# rs422.net
KiCad netlist of a schematic drawn in EAGLE
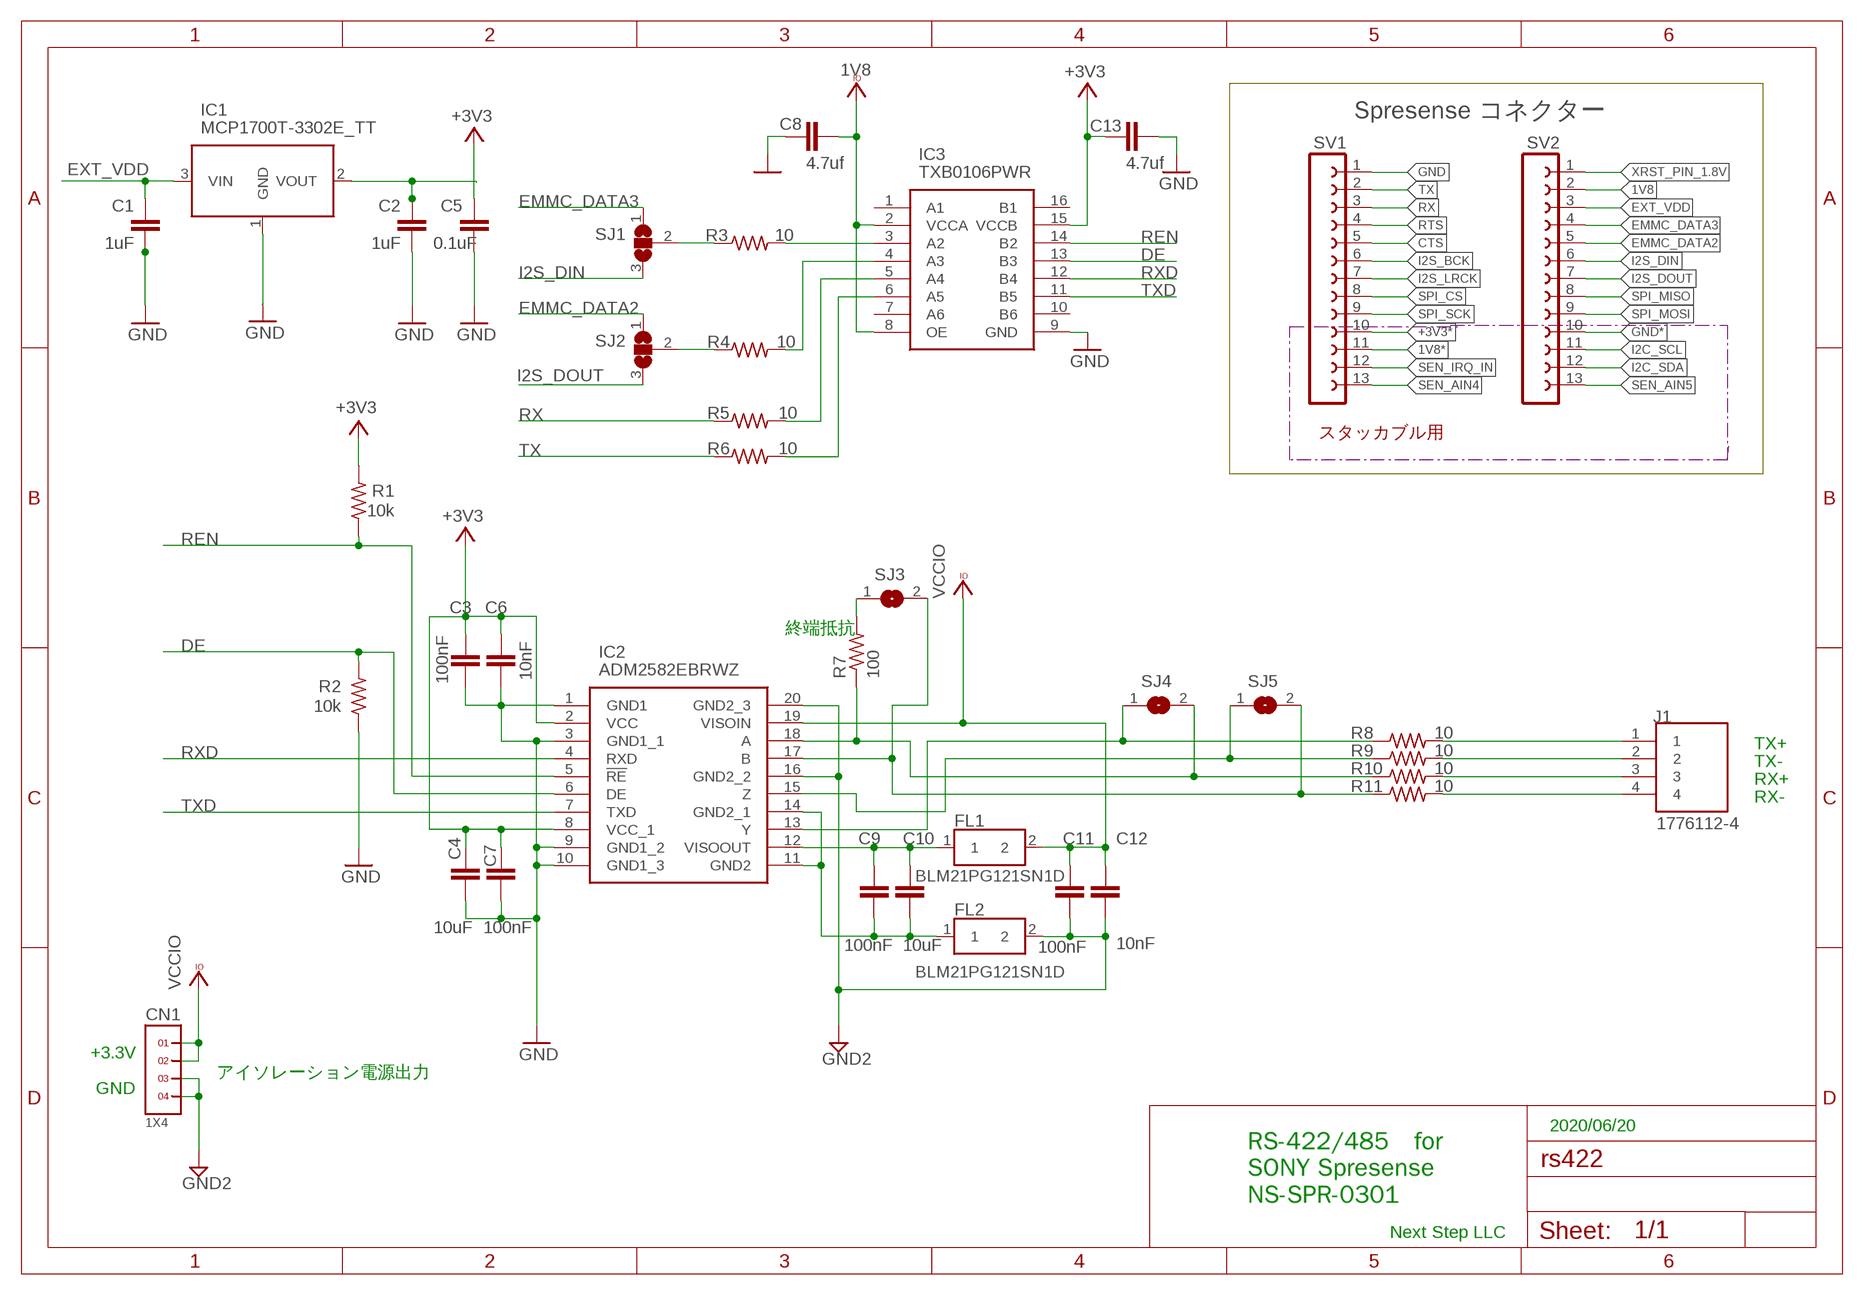
[diagram p0: schematic, sheet 1]

(export (version "E")
  (design (tool "Eeschema 10.0.6"))
  (components
    (comp (ref "C1")
      (value "1uF")
      (footprint "eagle-import:C0603K")
      (libsource (lib "eagle-import") (part "C-EUC0603K"))
    )
    (comp (ref "C2")
      (value "1uF")
      (footprint "eagle-import:C0603K")
      (libsource (lib "eagle-import") (part "C-EUC0603K"))
    )
    (comp (ref "C3")
      (value "100nF")
      (footprint "eagle-import:C0603K")
      (libsource (lib "eagle-import") (part "C-EUC0603K"))
    )
    (comp (ref "C4")
      (value "10uF")
      (footprint "eagle-import:C0603K")
      (libsource (lib "eagle-import") (part "C-EUC0603K"))
    )
    (comp (ref "C5")
      (value "0.1uF")
      (footprint "eagle-import:C0603K")
      (libsource (lib "eagle-import") (part "C-EUC0603K"))
    )
    (comp (ref "C6")
      (value "10nF")
      (footprint "eagle-import:C0603K")
      (libsource (lib "eagle-import") (part "C-EUC0603K"))
    )
    (comp (ref "C7")
      (value "100nF")
      (footprint "eagle-import:C0603K")
      (libsource (lib "eagle-import") (part "C-EUC0603K"))
    )
    (comp (ref "C8")
      (value "4.7uf")
      (footprint "eagle-import:C0603K")
      (libsource (lib "eagle-import") (part "C-EUC0603K"))
    )
    (comp (ref "C9")
      (value "100nF")
      (footprint "eagle-import:C0603K")
      (libsource (lib "eagle-import") (part "C-EUC0603K"))
    )
    (comp (ref "C10")
      (value "10uF")
      (footprint "eagle-import:C0603K")
      (libsource (lib "eagle-import") (part "C-EUC0603K"))
    )
    (comp (ref "C11")
      (value "100nF")
      (footprint "eagle-import:C0603K")
      (libsource (lib "eagle-import") (part "C-EUC0603K"))
    )
    (comp (ref "C12")
      (value "10nF")
      (footprint "eagle-import:C0603K")
      (libsource (lib "eagle-import") (part "C-EUC0603K"))
    )
    (comp (ref "C13")
      (value "4.7uf")
      (footprint "eagle-import:C0603K")
      (libsource (lib "eagle-import") (part "C-EUC0603K"))
    )
    (comp (ref "CN1")
      (value "1X4")
      (footprint "eagle-import:1X4")
      (libsource (lib "eagle-import") (part "1X4"))
    )
    (comp (ref "FL1")
      (value "BLM21PG121SN1D")
      (footprint "eagle-import:BEADC2012X105N")
      (fields (field (name "MOUSER_PART_NUMBER") "81-BLM21PG121SN1D"))
      (libsource (lib "eagle-import") (part "BLM21PG121SN1D"))
    )
    (comp (ref "FL2")
      (value "BLM21PG121SN1D")
      (footprint "eagle-import:BEADC2012X105N")
      (fields (field (name "MOUSER_PART_NUMBER") "81-BLM21PG121SN1D"))
      (libsource (lib "eagle-import") (part "BLM21PG121SN1D"))
    )
    (comp (ref "IC1")
      (value "MCP1700T-3302E_TT")
      (footprint "eagle-import:SOT95P237X112-3N")
      (fields
        (field (name "MANUFACTURER_PART_NUMBER") "MCP1700T-3302E/TT")
        (field (name "MOUSER_PART_NUMBER") "579-MCP1700T3302E/TT")
      )
      (libsource (lib "eagle-import") (part "MCP1700T-3302E_TT"))
    )
    (comp (ref "IC2")
      (value "ADM2582EBRWZ")
      (footprint "eagle-import:SOIC127P1032X265-20N")
      (fields (field (name "MOUSER_PART_NUMBER") "584-ADM2582EBRWZ"))
      (libsource (lib "eagle-import") (part "ADM2582EBRWZ"))
    )
    (comp (ref "IC3")
      (value "TXB0106PWR")
      (footprint "eagle-import:SOP65P640X120-16N")
      (fields (field (name "MOUSER_PART_NUMBER") "595-TXB0106PWR"))
      (libsource (lib "eagle-import") (part "TXB0106PWR"))
    )
    (comp (ref "J1")
      (value "1776112-4")
      (footprint "eagle-import:TE_1776112-4")
      (fields (field (name "MF") "TE Connectivity"))
      (libsource (lib "eagle-import") (part "1776112-4"))
    )
    (comp (ref "R1")
      (value "10k")
      (footprint "eagle-import:R0603")
      (libsource (lib "eagle-import") (part "R-US_R0603"))
    )
    (comp (ref "R2")
      (value "10k")
      (footprint "eagle-import:R0603")
      (libsource (lib "eagle-import") (part "R-US_R0603"))
    )
    (comp (ref "R3")
      (value "10")
      (footprint "eagle-import:R0603")
      (libsource (lib "eagle-import") (part "R-US_R0603"))
    )
    (comp (ref "R4")
      (value "10")
      (footprint "eagle-import:R0603")
      (libsource (lib "eagle-import") (part "R-US_R0603"))
    )
    (comp (ref "R5")
      (value "10")
      (footprint "eagle-import:R0603")
      (libsource (lib "eagle-import") (part "R-US_R0603"))
    )
    (comp (ref "R6")
      (value "10")
      (footprint "eagle-import:R0603")
      (libsource (lib "eagle-import") (part "R-US_R0603"))
    )
    (comp (ref "R7")
      (value "100")
      (footprint "eagle-import:R0603")
      (libsource (lib "eagle-import") (part "R-US_R0603"))
    )
    (comp (ref "R8")
      (value "10")
      (footprint "eagle-import:R0603")
      (libsource (lib "eagle-import") (part "R-US_R0603"))
    )
    (comp (ref "R9")
      (value "10")
      (footprint "eagle-import:R0603")
      (libsource (lib "eagle-import") (part "R-US_R0603"))
    )
    (comp (ref "R10")
      (value "10")
      (footprint "eagle-import:R0603")
      (libsource (lib "eagle-import") (part "R-US_R0603"))
    )
    (comp (ref "R11")
      (value "10")
      (footprint "eagle-import:R0603")
      (libsource (lib "eagle-import") (part "R-US_R0603"))
    )
    (comp (ref "SJ1")
      (value "SJ2W")
      (footprint "eagle-import:SJ_2")
      (libsource (lib "eagle-import") (part "SJ2W"))
    )
    (comp (ref "SJ2")
      (value "SJ2W")
      (footprint "eagle-import:SJ_2")
      (libsource (lib "eagle-import") (part "SJ2W"))
    )
    (comp (ref "SJ3") (value "SJ") (footprint "eagle-import:SJ") (libsource (lib "eagle-import") (part "SJ")))
    (comp (ref "SJ4") (value "SJ") (footprint "eagle-import:SJ") (libsource (lib "eagle-import") (part "SJ")))
    (comp (ref "SJ5") (value "SJ") (footprint "eagle-import:SJ") (libsource (lib "eagle-import") (part "SJ")))
    (comp (ref "SV1")
      (value "FE13-1")
      (footprint "eagle-import:FE13")
      (libsource (lib "eagle-import") (part "FE13-1"))
    )
    (comp (ref "SV2")
      (value "FE13-1")
      (footprint "eagle-import:FE13")
      (libsource (lib "eagle-import") (part "FE13-1"))
    )
  )
  (nets
    (net (code "1") (name "+3V3") (class "Default")
      (node (ref "C13") (pin "1") (pinfunction "1_1") (pintype "passive"))
      (node (ref "C2") (pin "1") (pinfunction "1_1") (pintype "passive"))
      (node (ref "C3") (pin "1") (pinfunction "1_1") (pintype "passive"))
      (node (ref "C4") (pin "1") (pinfunction "1_1") (pintype "passive"))
      (node (ref "C5") (pin "1") (pinfunction "1_1") (pintype "passive"))
      (node (ref "C6") (pin "1") (pinfunction "1_1") (pintype "passive"))
      (node (ref "C7") (pin "1") (pinfunction "1_1") (pintype "passive"))
      (node (ref "IC1") (pin "2") (pinfunction "VOUT_2") (pintype "output"))
      (node (ref "IC2") (pin "2") (pinfunction "VCC_2") (pintype "power_in"))
      (node (ref "IC2") (pin "8") (pinfunction "VCC_1_8") (pintype "power_in"))
      (node (ref "IC3") (pin "15") (pinfunction "VCCB_15") (pintype "power_in"))
      (node (ref "R1") (pin "2") (pinfunction "2_2") (pintype "passive"))
    )
    (net (code "2") (name "+3V3*") (class "Default")
      (node (ref "SV1") (pin "10") (pinfunction "10_10") (pintype "passive"))
    )
    (net (code "3") (name "/DE") (class "Default")
      (node (ref "IC2") (pin "6") (pinfunction "DE_6") (pintype "bidirectional"))
      (node (ref "IC3") (pin "13") (pinfunction "B3_13") (pintype "bidirectional"))
      (node (ref "R2") (pin "2") (pinfunction "2_2") (pintype "passive"))
    )
    (net (code "4") (name "/REN") (class "Default")
      (node (ref "IC2") (pin "5") (pinfunction "~{RE}_5") (pintype "bidirectional"))
      (node (ref "IC3") (pin "14") (pinfunction "B2_14") (pintype "bidirectional"))
      (node (ref "R1") (pin "1") (pinfunction "1_1") (pintype "passive"))
    )
    (net (code "5") (name "/RXD") (class "Default")
      (node (ref "IC2") (pin "4") (pinfunction "RXD_4") (pintype "bidirectional"))
      (node (ref "IC3") (pin "12") (pinfunction "B4_12") (pintype "bidirectional"))
    )
    (net (code "6") (name "/TXD") (class "Default")
      (node (ref "IC2") (pin "7") (pinfunction "TXD_7") (pintype "bidirectional"))
      (node (ref "IC3") (pin "11") (pinfunction "B5_11") (pintype "bidirectional"))
    )
    (net (code "7") (name "1V8") (class "Default")
      (node (ref "C8") (pin "2") (pinfunction "2_2") (pintype "passive"))
      (node (ref "IC3") (pin "2") (pinfunction "VCCA_2") (pintype "power_in"))
      (node (ref "IC3") (pin "8") (pinfunction "OE_8") (pintype "bidirectional"))
      (node (ref "SV2") (pin "2") (pinfunction "2_2") (pintype "passive"))
    )
    (net (code "8") (name "1V8*") (class "Default")
      (node (ref "SV1") (pin "11") (pinfunction "11_11") (pintype "passive"))
    )
    (net (code "9") (name "CTS") (class "Default")
      (node (ref "SV1") (pin "5") (pinfunction "5_5") (pintype "passive"))
    )
    (net (code "10") (name "EMMC_DATA2") (class "Default")
      (node (ref "SJ2") (pin "1") (pinfunction "1_1") (pintype "passive"))
      (node (ref "SV2") (pin "5") (pinfunction "5_5") (pintype "passive"))
    )
    (net (code "11") (name "EMMC_DATA3") (class "Default")
      (node (ref "SJ1") (pin "1") (pinfunction "1_1") (pintype "passive"))
      (node (ref "SV2") (pin "4") (pinfunction "4_4") (pintype "passive"))
    )
    (net (code "12") (name "EXT_VDD") (class "Default")
      (node (ref "C1") (pin "1") (pinfunction "1_1") (pintype "passive"))
      (node (ref "IC1") (pin "3") (pinfunction "VIN_3") (pintype "input"))
      (node (ref "SV2") (pin "3") (pinfunction "3_3") (pintype "passive"))
    )
    (net (code "13") (name "GND") (class "Default")
      (node (ref "C1") (pin "2") (pinfunction "2_2") (pintype "passive"))
      (node (ref "C13") (pin "2") (pinfunction "2_2") (pintype "passive"))
      (node (ref "C2") (pin "2") (pinfunction "2_2") (pintype "passive"))
      (node (ref "C3") (pin "2") (pinfunction "2_2") (pintype "passive"))
      (node (ref "C4") (pin "2") (pinfunction "2_2") (pintype "passive"))
      (node (ref "C5") (pin "2") (pinfunction "2_2") (pintype "passive"))
      (node (ref "C6") (pin "2") (pinfunction "2_2") (pintype "passive"))
      (node (ref "C7") (pin "2") (pinfunction "2_2") (pintype "passive"))
      (node (ref "C8") (pin "1") (pinfunction "1_1") (pintype "passive"))
      (node (ref "IC1") (pin "1") (pinfunction "GND_1") (pintype "power_in"))
      (node (ref "IC2") (pin "1") (pinfunction "GND1_1") (pintype "power_in"))
      (node (ref "IC2") (pin "10") (pinfunction "GND1_3_10") (pintype "power_in"))
      (node (ref "IC2") (pin "3") (pinfunction "GND1_1_3") (pintype "power_in"))
      (node (ref "IC2") (pin "9") (pinfunction "GND1_2_9") (pintype "power_in"))
      (node (ref "IC3") (pin "9") (pinfunction "GND_9") (pintype "power_in"))
      (node (ref "R2") (pin "1") (pinfunction "1_1") (pintype "passive"))
      (node (ref "SV1") (pin "1") (pinfunction "1_1") (pintype "passive"))
    )
    (net (code "14") (name "GND*") (class "Default")
      (node (ref "SV2") (pin "10") (pinfunction "10_10") (pintype "passive"))
    )
    (net (code "15") (name "GND2") (class "Default")
      (node (ref "C11") (pin "2") (pinfunction "2_2") (pintype "passive"))
      (node (ref "C12") (pin "2") (pinfunction "2_2") (pintype "passive"))
      (node (ref "CN1") (pin "3") (pinfunction "3_3") (pintype "bidirectional"))
      (node (ref "CN1") (pin "4") (pinfunction "4_4") (pintype "bidirectional"))
      (node (ref "FL2") (pin "2") (pinfunction "2_2") (pintype "bidirectional"))
      (node (ref "IC2") (pin "16") (pinfunction "GND2_2_16") (pintype "power_in"))
      (node (ref "IC2") (pin "20") (pinfunction "GND2_3_20") (pintype "power_in"))
    )
    (net (code "16") (name "I2C_SCL") (class "Default")
      (node (ref "SV2") (pin "11") (pinfunction "11_11") (pintype "passive"))
    )
    (net (code "17") (name "I2C_SDA") (class "Default")
      (node (ref "SV2") (pin "12") (pinfunction "12_12") (pintype "passive"))
    )
    (net (code "18") (name "I2S_BCK") (class "Default")
      (node (ref "SV1") (pin "6") (pinfunction "6_6") (pintype "passive"))
    )
    (net (code "19") (name "I2S_DIN") (class "Default")
      (node (ref "SJ1") (pin "3") (pinfunction "3_3") (pintype "passive"))
      (node (ref "SV2") (pin "6") (pinfunction "6_6") (pintype "passive"))
    )
    (net (code "20") (name "I2S_DOUT") (class "Default")
      (node (ref "SJ2") (pin "3") (pinfunction "3_3") (pintype "passive"))
      (node (ref "SV2") (pin "7") (pinfunction "7_7") (pintype "passive"))
    )
    (net (code "21") (name "I2S_LRCK") (class "Default")
      (node (ref "SV1") (pin "7") (pinfunction "7_7") (pintype "passive"))
    )
    (net (code "22") (name "Net-(IC2-A)") (class "Default")
      (node (ref "IC2") (pin "18") (pinfunction "A_18") (pintype "bidirectional"))
      (node (ref "R10") (pin "1") (pinfunction "1_1") (pintype "passive"))
      (node (ref "R7") (pin "1") (pinfunction "1_1") (pintype "passive"))
      (node (ref "SJ4") (pin "2") (pinfunction "2_2") (pintype "passive"))
    )
    (net (code "23") (name "Net-(IC2-B)") (class "Default")
      (node (ref "IC2") (pin "17") (pinfunction "B_17") (pintype "bidirectional"))
      (node (ref "R11") (pin "1") (pinfunction "1_1") (pintype "passive"))
      (node (ref "SJ3") (pin "2") (pinfunction "2_2") (pintype "passive"))
      (node (ref "SJ5") (pin "2") (pinfunction "2_2") (pintype "passive"))
    )
    (net (code "24") (name "Net-(IC2-GND2)") (class "Default")
      (node (ref "C10") (pin "2") (pinfunction "2_2") (pintype "passive"))
      (node (ref "C9") (pin "2") (pinfunction "2_2") (pintype "passive"))
      (node (ref "FL2") (pin "1") (pinfunction "1_1") (pintype "bidirectional"))
      (node (ref "IC2") (pin "11") (pinfunction "GND2_11") (pintype "power_in"))
      (node (ref "IC2") (pin "14") (pinfunction "GND2_1_14") (pintype "power_in"))
    )
    (net (code "25") (name "Net-(IC2-VISOOUT)") (class "Default")
      (node (ref "C10") (pin "1") (pinfunction "1_1") (pintype "passive"))
      (node (ref "C9") (pin "1") (pinfunction "1_1") (pintype "passive"))
      (node (ref "FL1") (pin "1") (pinfunction "1_1") (pintype "bidirectional"))
      (node (ref "IC2") (pin "12") (pinfunction "VISOOUT_12") (pintype "output"))
    )
    (net (code "26") (name "Net-(IC2-Y)") (class "Default")
      (node (ref "IC2") (pin "13") (pinfunction "Y_13") (pintype "bidirectional"))
      (node (ref "R8") (pin "1") (pinfunction "1_1") (pintype "passive"))
      (node (ref "SJ4") (pin "1") (pinfunction "1_1") (pintype "passive"))
    )
    (net (code "27") (name "Net-(IC2-Z)") (class "Default")
      (node (ref "IC2") (pin "15") (pinfunction "Z_15") (pintype "bidirectional"))
      (node (ref "R9") (pin "1") (pinfunction "1_1") (pintype "passive"))
      (node (ref "SJ5") (pin "1") (pinfunction "1_1") (pintype "passive"))
    )
    (net (code "28") (name "Net-(IC3-A2)") (class "Default")
      (node (ref "IC3") (pin "3") (pinfunction "A2_3") (pintype "bidirectional"))
      (node (ref "R3") (pin "2") (pinfunction "2_2") (pintype "passive"))
    )
    (net (code "29") (name "Net-(IC3-A3)") (class "Default")
      (node (ref "IC3") (pin "4") (pinfunction "A3_4") (pintype "bidirectional"))
      (node (ref "R4") (pin "2") (pinfunction "2_2") (pintype "passive"))
    )
    (net (code "30") (name "Net-(IC3-A4)") (class "Default")
      (node (ref "IC3") (pin "5") (pinfunction "A4_5") (pintype "bidirectional"))
      (node (ref "R5") (pin "2") (pinfunction "2_2") (pintype "passive"))
    )
    (net (code "31") (name "Net-(IC3-A5)") (class "Default")
      (node (ref "IC3") (pin "6") (pinfunction "A5_6") (pintype "bidirectional"))
      (node (ref "R6") (pin "2") (pinfunction "2_2") (pintype "passive"))
    )
    (net (code "32") (name "Net-(J1-Pad1)") (class "Default")
      (node (ref "J1") (pin "1") (pinfunction "1_1") (pintype "passive"))
      (node (ref "R8") (pin "2") (pinfunction "2_2") (pintype "passive"))
    )
    (net (code "33") (name "Net-(J1-Pad2)") (class "Default")
      (node (ref "J1") (pin "2") (pinfunction "2_2") (pintype "passive"))
      (node (ref "R9") (pin "2") (pinfunction "2_2") (pintype "passive"))
    )
    (net (code "34") (name "Net-(J1-Pad3)") (class "Default")
      (node (ref "J1") (pin "3") (pinfunction "3_3") (pintype "passive"))
      (node (ref "R10") (pin "2") (pinfunction "2_2") (pintype "passive"))
    )
    (net (code "35") (name "Net-(J1-Pad4)") (class "Default")
      (node (ref "J1") (pin "4") (pinfunction "4_4") (pintype "passive"))
      (node (ref "R11") (pin "2") (pinfunction "2_2") (pintype "passive"))
    )
    (net (code "36") (name "Net-(R3-Pad1)") (class "Default")
      (node (ref "R3") (pin "1") (pinfunction "1_1") (pintype "passive"))
      (node (ref "SJ1") (pin "2") (pinfunction "2_2") (pintype "passive"))
    )
    (net (code "37") (name "Net-(R4-Pad1)") (class "Default")
      (node (ref "R4") (pin "1") (pinfunction "1_1") (pintype "passive"))
      (node (ref "SJ2") (pin "2") (pinfunction "2_2") (pintype "passive"))
    )
    (net (code "38") (name "Net-(R7-Pad2)") (class "Default")
      (node (ref "R7") (pin "2") (pinfunction "2_2") (pintype "passive"))
      (node (ref "SJ3") (pin "1") (pinfunction "1_1") (pintype "passive"))
    )
    (net (code "39") (name "RTS") (class "Default")
      (node (ref "SV1") (pin "4") (pinfunction "4_4") (pintype "passive"))
    )
    (net (code "40") (name "RX") (class "Default")
      (node (ref "R5") (pin "1") (pinfunction "1_1") (pintype "passive"))
      (node (ref "SV1") (pin "3") (pinfunction "3_3") (pintype "passive"))
    )
    (net (code "41") (name "SEN_AIN4") (class "Default")
      (node (ref "SV1") (pin "13") (pinfunction "13_13") (pintype "passive"))
    )
    (net (code "42") (name "SEN_AIN5") (class "Default")
      (node (ref "SV2") (pin "13") (pinfunction "13_13") (pintype "passive"))
    )
    (net (code "43") (name "SEN_IRQ_IN") (class "Default")
      (node (ref "SV1") (pin "12") (pinfunction "12_12") (pintype "passive"))
    )
    (net (code "44") (name "SPI_CS") (class "Default")
      (node (ref "SV1") (pin "8") (pinfunction "8_8") (pintype "passive"))
    )
    (net (code "45") (name "SPI_MISO") (class "Default")
      (node (ref "SV2") (pin "8") (pinfunction "8_8") (pintype "passive"))
    )
    (net (code "46") (name "SPI_MOSI") (class "Default")
      (node (ref "SV2") (pin "9") (pinfunction "9_9") (pintype "passive"))
    )
    (net (code "47") (name "SPI_SCK") (class "Default")
      (node (ref "SV1") (pin "9") (pinfunction "9_9") (pintype "passive"))
    )
    (net (code "48") (name "TX") (class "Default")
      (node (ref "R6") (pin "1") (pinfunction "1_1") (pintype "passive"))
      (node (ref "SV1") (pin "2") (pinfunction "2_2") (pintype "passive"))
    )
    (net (code "49") (name "VCCIO") (class "Default")
      (node (ref "C11") (pin "1") (pinfunction "1_1") (pintype "passive"))
      (node (ref "C12") (pin "1") (pinfunction "1_1") (pintype "passive"))
      (node (ref "CN1") (pin "1") (pinfunction "1_1") (pintype "bidirectional"))
      (node (ref "CN1") (pin "2") (pinfunction "2_2") (pintype "bidirectional"))
      (node (ref "FL1") (pin "2") (pinfunction "2_2") (pintype "bidirectional"))
      (node (ref "IC2") (pin "19") (pinfunction "VISOIN_19") (pintype "input"))
    )
    (net (code "50") (name "XRST_PIN_1.8V") (class "Default")
      (node (ref "SV2") (pin "1") (pinfunction "1_1") (pintype "passive"))
    )
    (net (code "51") (name "unconnected-(IC3-A1-Pad1)") (class "Default")
      (node (ref "IC3") (pin "1") (pinfunction "A1_1") (pintype "bidirectional"))
    )
    (net (code "52") (name "unconnected-(IC3-A6-Pad7)") (class "Default")
      (node (ref "IC3") (pin "7") (pinfunction "A6_7") (pintype "bidirectional"))
    )
    (net (code "53") (name "unconnected-(IC3-B1-Pad16)") (class "Default")
      (node (ref "IC3") (pin "16") (pinfunction "B1_16") (pintype "bidirectional"))
    )
    (net (code "54") (name "unconnected-(IC3-B6-Pad10)") (class "Default")
      (node (ref "IC3") (pin "10") (pinfunction "B6_10") (pintype "bidirectional"))
    )
  )
)
